# schematic.net
KiCad netlist of a schematic drawn in EAGLE
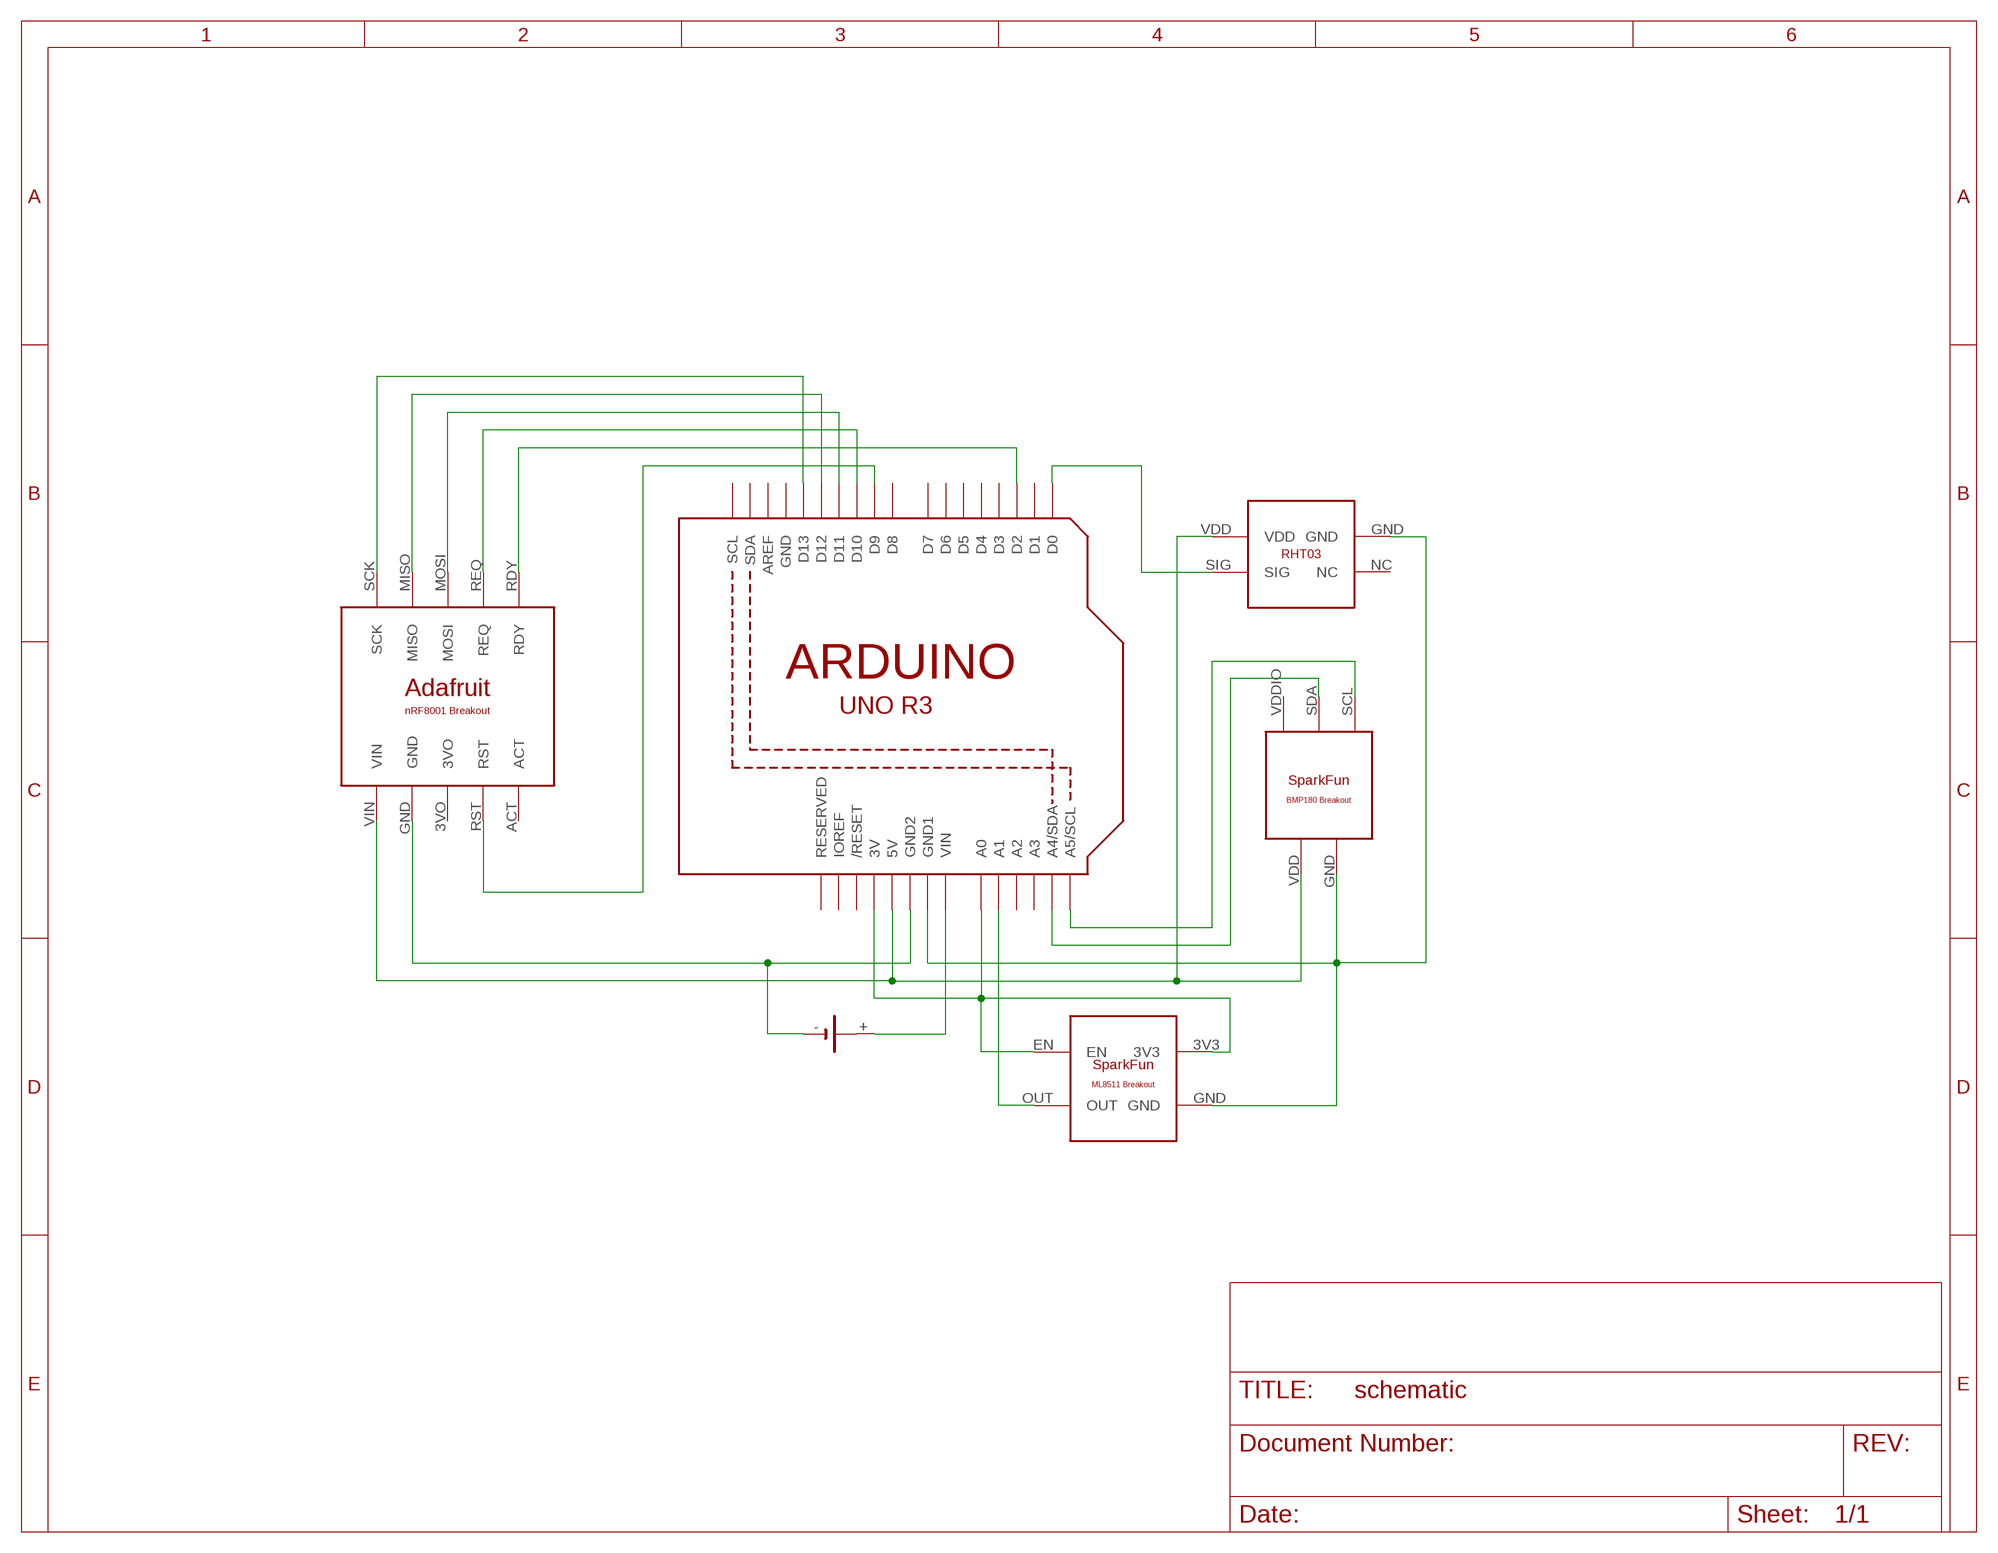
[diagram p0: schematic, sheet 1]

(export (version "E")
  (design (tool "Eeschema 10.0.6"))
  (components
    (comp (ref "BAT")
      (value "1V60R")
      (footprint "eagle-import:1V60R")
      (libsource (lib "eagle-import") (part "1V60R"))
    )
    (comp (ref "U$1")
      (value "ADAFRUIT_NRF8001_BREAKOUT")
      (footprint "eagle-import:ADAFRUIT_NRF8001_BREAKOUT_HEADERS")
      (libsource (lib "eagle-import") (part "ADAFRUIT_NRF8001_BREAKOUT"))
    )
    (comp (ref "U$2")
      (value "SPARKFUN_BMP180_BREAKOUT")
      (footprint "eagle-import:SPARKFUN_BMP180_BREAKOUT_HEADERS")
      (libsource (lib "eagle-import") (part "SPARKFUN_BMP180_BREAKOUT"))
    )
    (comp (ref "U$3")
      (value "RHT03")
      (footprint "eagle-import:RHT03_HEADERS")
      (libsource (lib "eagle-import") (part "RHT03"))
    )
    (comp (ref "U$4")
      (value "SPARKFUN_ML8511_BREAKOUT")
      (footprint "eagle-import:SPARKFUN_ML8511_BREAKOUT_HEADERS")
      (libsource (lib "eagle-import") (part "SPARKFUN_ML8511_BREAKOUT"))
    )
    (comp (ref "U1")
      (value "ARDUINOR3-DIMENSION")
      (footprint "eagle-import:ARDUINOR3")
      (libsource (lib "eagle-import") (part "ARDUINOR3-DIMENSION"))
    )
  )
  (nets
    (net (code "1") (name "/GND") (class "Default")
      (node (ref "U1") (pin "GND") (pinfunction "GND_GND") (pintype "power_in"))
    )
    (net (code "2") (name "Net-(BAT-Pad+)") (class "Default")
      (node (ref "BAT") (pin "+") (pinfunction "+_+") (pintype "passive"))
      (node (ref "U1") (pin "VIN") (pinfunction "VIN_VIN") (pintype "power_in"))
    )
    (net (code "3") (name "Net-(BAT-Pad-)") (class "Default")
      (node (ref "BAT") (pin "-") (pinfunction "-_-") (pintype "passive"))
      (node (ref "U$1") (pin "GND") (pinfunction "GND_GND") (pintype "bidirectional"))
      (node (ref "U1") (pin "GND2") (pinfunction "GND2_GND2") (pintype "power_in"))
    )
    (net (code "4") (name "Net-(U$1-PadMISO)") (class "Default")
      (node (ref "U$1") (pin "MISO") (pinfunction "MISO_MISO") (pintype "bidirectional"))
      (node (ref "U1") (pin "D12") (pinfunction "D12_D12") (pintype "bidirectional"))
    )
    (net (code "5") (name "Net-(U$1-PadMOSI)") (class "Default")
      (node (ref "U$1") (pin "MOSI") (pinfunction "MOSI_MOSI") (pintype "bidirectional"))
      (node (ref "U1") (pin "D11") (pinfunction "D11_D11") (pintype "bidirectional"))
    )
    (net (code "6") (name "Net-(U$1-PadRDY)") (class "Default")
      (node (ref "U$1") (pin "RDY") (pinfunction "RDY_RDY") (pintype "bidirectional"))
      (node (ref "U1") (pin "D2") (pinfunction "D2_D2") (pintype "bidirectional"))
    )
    (net (code "7") (name "Net-(U$1-PadREQ)") (class "Default")
      (node (ref "U$1") (pin "REQ") (pinfunction "REQ_REQ") (pintype "bidirectional"))
      (node (ref "U1") (pin "D10") (pinfunction "D10_D10") (pintype "bidirectional"))
    )
    (net (code "8") (name "Net-(U$1-PadRST)") (class "Default")
      (node (ref "U$1") (pin "RST") (pinfunction "RST_RST") (pintype "bidirectional"))
      (node (ref "U1") (pin "D9") (pinfunction "D9_D9") (pintype "bidirectional"))
    )
    (net (code "9") (name "Net-(U$1-PadSCK)") (class "Default")
      (node (ref "U$1") (pin "SCK") (pinfunction "SCK_SCK") (pintype "bidirectional"))
      (node (ref "U1") (pin "D13") (pinfunction "D13_D13") (pintype "bidirectional"))
    )
    (net (code "10") (name "Net-(U$1-PadVIN)") (class "Default")
      (node (ref "U$1") (pin "VIN") (pinfunction "VIN_VIN") (pintype "bidirectional"))
      (node (ref "U$2") (pin "VDD") (pinfunction "VDD_VDD") (pintype "bidirectional"))
      (node (ref "U$3") (pin "VDD") (pinfunction "VDD_VDD") (pintype "power_in"))
      (node (ref "U1") (pin "5V") (pinfunction "5V_5V") (pintype "power_in"))
    )
    (net (code "11") (name "Net-(U$2-PadGND)") (class "Default")
      (node (ref "U$2") (pin "GND") (pinfunction "GND_GND") (pintype "bidirectional"))
      (node (ref "U$3") (pin "GND") (pinfunction "GND_GND") (pintype "power_in"))
      (node (ref "U$4") (pin "GND") (pinfunction "GND_GND") (pintype "bidirectional"))
      (node (ref "U1") (pin "GND1") (pinfunction "GND1_GND1") (pintype "power_in"))
    )
    (net (code "12") (name "Net-(U$3-PadSIG)") (class "Default")
      (node (ref "U$3") (pin "SIG") (pinfunction "SIG_SIG") (pintype "bidirectional"))
      (node (ref "U1") (pin "D0") (pinfunction "D0_D0") (pintype "bidirectional"))
    )
    (net (code "13") (name "Net-(U$4-Pad3V3)") (class "Default")
      (node (ref "U$4") (pin "3V3") (pinfunction "3V3_3V3") (pintype "bidirectional"))
      (node (ref "U$4") (pin "EN") (pinfunction "EN_EN") (pintype "bidirectional"))
      (node (ref "U1") (pin "3V") (pinfunction "3V_3V") (pintype "power_in"))
      (node (ref "U1") (pin "A0") (pinfunction "A0_A0") (pintype "bidirectional"))
    )
    (net (code "14") (name "Net-(U$4-PadOUT)") (class "Default")
      (node (ref "U$4") (pin "OUT") (pinfunction "OUT_OUT") (pintype "bidirectional"))
      (node (ref "U1") (pin "A1") (pinfunction "A1_A1") (pintype "bidirectional"))
    )
    (net (code "15") (name "Net-(U1-A4{slash}SDA)") (class "Default")
      (node (ref "U$2") (pin "SDA") (pinfunction "SDA_SDA") (pintype "bidirectional"))
      (node (ref "U1") (pin "A4") (pinfunction "A4/SDA_A4") (pintype "bidirectional"))
    )
    (net (code "16") (name "Net-(U1-A5{slash}SCL)") (class "Default")
      (node (ref "U$2") (pin "SCL") (pinfunction "SCL_SCL") (pintype "bidirectional"))
      (node (ref "U1") (pin "A5") (pinfunction "A5/SCL_A5") (pintype "bidirectional"))
    )
    (net (code "17") (name "unconnected-(BAT-+-Pad+@1)") (class "Default")
      (node (ref "BAT") (pin "+@1") (pinfunction "+_+@1") (pintype "passive"))
    )
    (net (code "18") (name "unconnected-(U$1-Pad3VO)") (class "Default")
      (node (ref "U$1") (pin "3VO") (pinfunction "3VO_3VO") (pintype "bidirectional"))
    )
    (net (code "19") (name "unconnected-(U$1-PadACT)") (class "Default")
      (node (ref "U$1") (pin "ACT") (pinfunction "ACT_ACT") (pintype "bidirectional"))
    )
    (net (code "20") (name "unconnected-(U$2-PadVDDIO)") (class "Default")
      (node (ref "U$2") (pin "VDDIO") (pinfunction "VDDIO_VDDIO") (pintype "bidirectional"))
    )
    (net (code "21") (name "unconnected-(U$3-PadNC)") (class "Default")
      (node (ref "U$3") (pin "NC") (pinfunction "NC_NC") (pintype "no_connect"))
    )
    (net (code "22") (name "unconnected-(U1-PadA2)") (class "Default")
      (node (ref "U1") (pin "A2") (pinfunction "A2_A2") (pintype "bidirectional"))
    )
    (net (code "23") (name "unconnected-(U1-PadA3)") (class "Default")
      (node (ref "U1") (pin "A3") (pinfunction "A3_A3") (pintype "bidirectional"))
    )
    (net (code "24") (name "unconnected-(U1-PadAREF)") (class "Default")
      (node (ref "U1") (pin "AREF") (pinfunction "AREF_AREF") (pintype "bidirectional"))
    )
    (net (code "25") (name "unconnected-(U1-PadD1)") (class "Default")
      (node (ref "U1") (pin "D1") (pinfunction "D1_D1") (pintype "bidirectional"))
    )
    (net (code "26") (name "unconnected-(U1-PadD3)") (class "Default")
      (node (ref "U1") (pin "D3") (pinfunction "D3_D3") (pintype "bidirectional"))
    )
    (net (code "27") (name "unconnected-(U1-PadD4)") (class "Default")
      (node (ref "U1") (pin "D4") (pinfunction "D4_D4") (pintype "bidirectional"))
    )
    (net (code "28") (name "unconnected-(U1-PadD5)") (class "Default")
      (node (ref "U1") (pin "D5") (pinfunction "D5_D5") (pintype "bidirectional"))
    )
    (net (code "29") (name "unconnected-(U1-PadD6)") (class "Default")
      (node (ref "U1") (pin "D6") (pinfunction "D6_D6") (pintype "bidirectional"))
    )
    (net (code "30") (name "unconnected-(U1-PadD7)") (class "Default")
      (node (ref "U1") (pin "D7") (pinfunction "D7_D7") (pintype "bidirectional"))
    )
    (net (code "31") (name "unconnected-(U1-PadD8)") (class "Default")
      (node (ref "U1") (pin "D8") (pinfunction "D8_D8") (pintype "bidirectional"))
    )
    (net (code "32") (name "unconnected-(U1-PadIOREF)") (class "Default")
      (node (ref "U1") (pin "IOREF") (pinfunction "IOREF_IOREF") (pintype "output"))
    )
    (net (code "33") (name "unconnected-(U1-PadRESERVED)") (class "Default")
      (node (ref "U1") (pin "RESERVED") (pinfunction "RESERVED_RESERVED") (pintype "no_connect"))
    )
    (net (code "34") (name "unconnected-(U1-PadSCL)") (class "Default")
      (node (ref "U1") (pin "SCL") (pinfunction "SCL_SCL") (pintype "bidirectional"))
    )
    (net (code "35") (name "unconnected-(U1-PadSDA)") (class "Default")
      (node (ref "U1") (pin "SDA") (pinfunction "SDA_SDA") (pintype "bidirectional"))
    )
    (net (code "36") (name "unconnected-(U1-{slash}RESET-PadRESET)") (class "Default")
      (node (ref "U1") (pin "RESET") (pinfunction "/RESET_RESET") (pintype "bidirectional"))
    )
  )
)
